# ELEKTRA-BENCH_v0_1-20240103.net
KiCad netlist of a schematic drawn in EAGLE
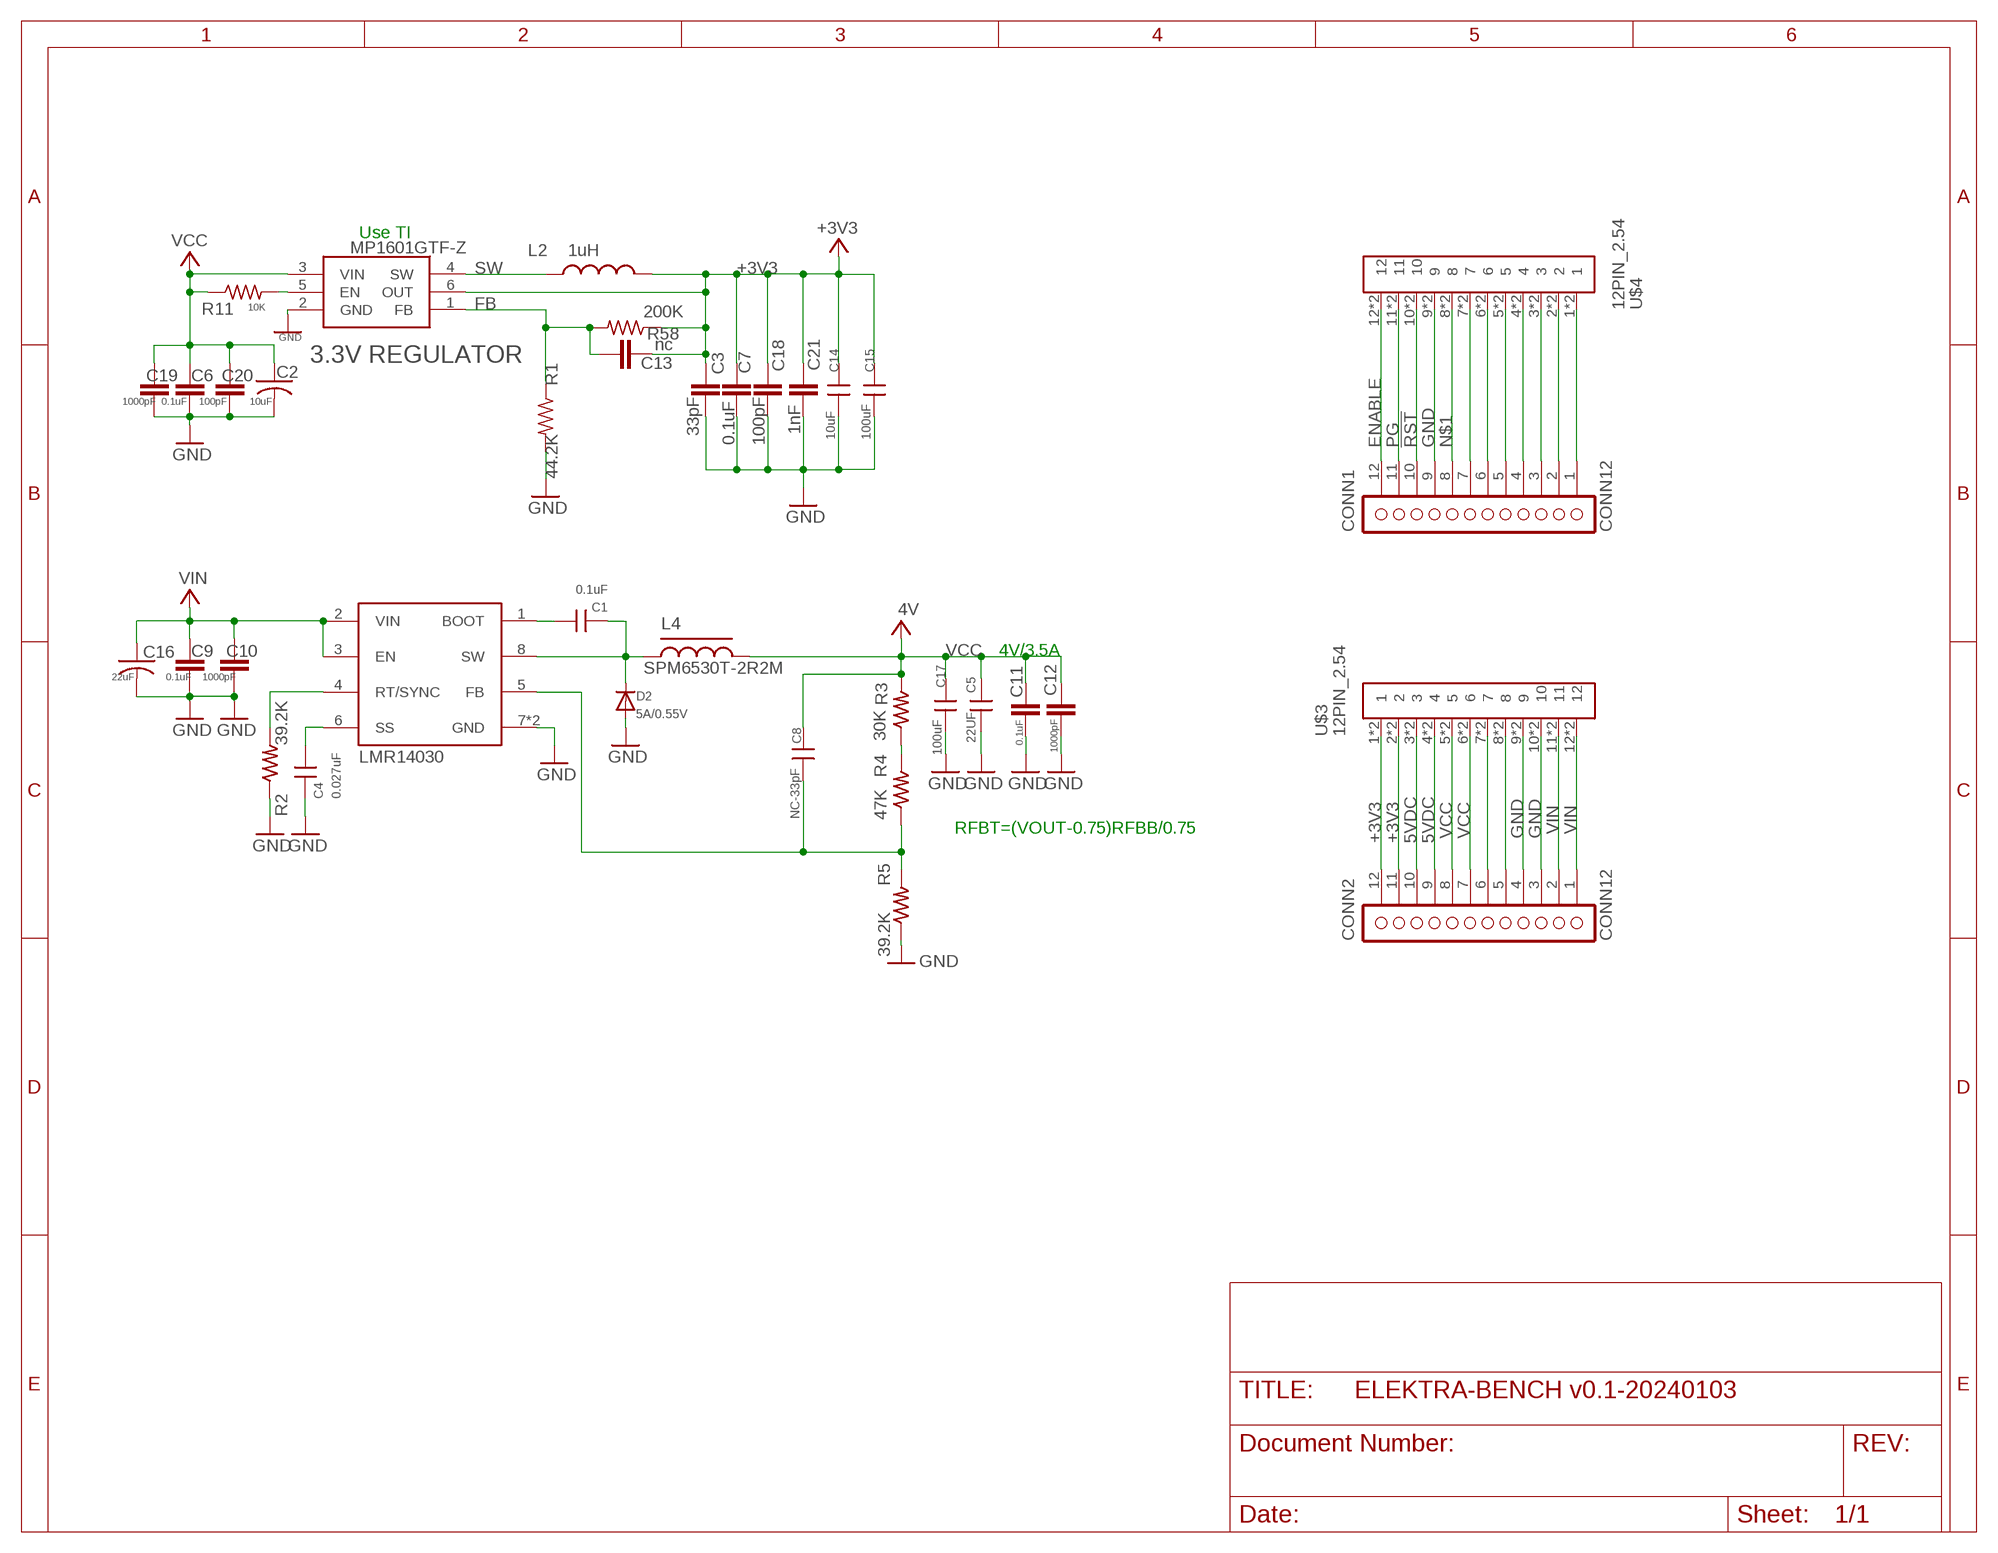
[diagram p0: schematic, sheet 1]

(export (version "E")
  (design (tool "Eeschema 10.0.6"))
  (components
    (comp (ref "C1")
      (value "0.1uF")
      (footprint "eagle-import:C0402")
      (libsource (lib "eagle-import") (part "particle SZ_21650216_CAP0402A"))
    )
    (comp (ref "C2")
      (value "10uF")
      (footprint "eagle-import:C0603_B")
      (libsource (lib "eagle-import") (part "C-US0603"))
    )
    (comp (ref "C3")
      (value "33pF")
      (footprint "eagle-import:C0402_B")
      (libsource (lib "eagle-import") (part "CAP_1"))
    )
    (comp (ref "C4")
      (value "0.027uF")
      (footprint "eagle-import:C0402")
      (libsource (lib "eagle-import") (part "particle SZ_21650216_CAP0402A"))
    )
    (comp (ref "C5")
      (value "22UF")
      (footprint "eagle-import:C0805")
      (libsource (lib "eagle-import") (part "CAPC0805"))
    )
    (comp (ref "C6")
      (value "0.1uF")
      (footprint "eagle-import:C0402_B")
      (libsource (lib "eagle-import") (part "CAP_1"))
    )
    (comp (ref "C7")
      (value "0.1uF")
      (footprint "eagle-import:C0402_B")
      (libsource (lib "eagle-import") (part "CAP_1"))
    )
    (comp (ref "C8")
      (value "NC-33pF")
      (footprint "eagle-import:C0402")
      (libsource (lib "eagle-import") (part "particle SZ_21650216_CAP0402A"))
    )
    (comp (ref "C9")
      (value "0.1uF")
      (footprint "eagle-import:C0402_B")
      (libsource (lib "eagle-import") (part "CAP_1"))
    )
    (comp (ref "C10")
      (value "1000pF")
      (footprint "eagle-import:C0402_B")
      (libsource (lib "eagle-import") (part "CAP_1"))
    )
    (comp (ref "C11")
      (value "0.1uF")
      (footprint "eagle-import:C0402_B")
      (libsource (lib "eagle-import") (part "CAP_1"))
    )
    (comp (ref "C12")
      (value "1000pF")
      (footprint "eagle-import:C0402_B")
      (libsource (lib "eagle-import") (part "CAP_1"))
    )
    (comp (ref "C13")
      (value "nc")
      (footprint "eagle-import:C0402_B")
      (libsource (lib "eagle-import") (part "CAP_1"))
    )
    (comp (ref "C14")
      (value "10uF")
      (footprint "eagle-import:C0805")
      (libsource (lib "eagle-import") (part "CAPC0805"))
    )
    (comp (ref "C15")
      (value "100uF")
      (footprint "eagle-import:C1206")
      (libsource (lib "eagle-import") (part "CAPC1206"))
    )
    (comp (ref "C16")
      (value "22uF")
      (footprint "eagle-import:C0603_B")
      (libsource (lib "eagle-import") (part "C-US0603"))
    )
    (comp (ref "C17")
      (value "100uF")
      (footprint "eagle-import:C1206")
      (libsource (lib "eagle-import") (part "CAPC1206"))
    )
    (comp (ref "C18")
      (value "100pF")
      (footprint "eagle-import:C0402_B")
      (libsource (lib "eagle-import") (part "CAP_1"))
    )
    (comp (ref "C19")
      (value "1000pF")
      (footprint "eagle-import:C0402_B")
      (libsource (lib "eagle-import") (part "CAP_1"))
    )
    (comp (ref "C20")
      (value "100pF")
      (footprint "eagle-import:C0402_B")
      (libsource (lib "eagle-import") (part "CAP_1"))
    )
    (comp (ref "C21")
      (value "1nF")
      (footprint "eagle-import:C0402_B")
      (libsource (lib "eagle-import") (part "CAP_1"))
    )
    (comp (ref "CONN1")
      (value "CONN12")
      (footprint "eagle-import:1X12_SMD_STRAIGHT")
      (libsource (lib "eagle-import") (part "CONN12"))
    )
    (comp (ref "CONN2")
      (value "CONN12")
      (footprint "eagle-import:1X12_SMD_STRAIGHT")
      (libsource (lib "eagle-import") (part "CONN12"))
    )
    (comp (ref "D2")
      (value "5A/0.55V")
      (footprint "eagle-import:SMADIODE")
      (libsource (lib "eagle-import") (part "DIODESMA"))
    )
    (comp (ref "L2")
      (value "1uH")
      (footprint "eagle-import:INDUCTOR-VLS-E")
      (libsource (lib "eagle-import") (part "INDUCTOR-SPARKFUNVLS3012ET-4R7M"))
    )
    (comp (ref "L4")
      (value "SPM6530T-2R2M")
      (footprint "eagle-import:INDCUTOR_SPM6530")
      (libsource (lib "eagle-import") (part "INDUCTOR"))
    )
    (comp (ref "R1")
      (value "44.2K")
      (footprint "eagle-import:R0402_B")
      (libsource (lib "eagle-import") (part "R-US_"))
    )
    (comp (ref "R2")
      (value "39.2K")
      (footprint "eagle-import:R-0402S")
      (libsource (lib "eagle-import") (part "RES0402S"))
    )
    (comp (ref "R3")
      (value "30K")
      (footprint "eagle-import:R-0402S")
      (libsource (lib "eagle-import") (part "RES0402S"))
    )
    (comp (ref "R4")
      (value "47K")
      (footprint "eagle-import:R-0402S")
      (libsource (lib "eagle-import") (part "RES0402S"))
    )
    (comp (ref "R5")
      (value "39.2K")
      (footprint "eagle-import:R-0402S")
      (libsource (lib "eagle-import") (part "RES0402S"))
    )
    (comp (ref "R11")
      (value "10K")
      (footprint "eagle-import:R0402_B")
      (libsource (lib "eagle-import") (part "Spark_R-US_"))
    )
    (comp (ref "R58")
      (value "200K")
      (footprint "eagle-import:R0402_B")
      (libsource (lib "eagle-import") (part "R-US_"))
    )
    (comp (ref "U$3")
      (value "12PIN_2.54")
      (footprint "eagle-import:12PIN_2.54")
      (libsource (lib "eagle-import") (part "12PIN_2.54"))
    )
    (comp (ref "U$4")
      (value "12PIN_2.54")
      (footprint "eagle-import:12PIN_2.54")
      (libsource (lib "eagle-import") (part "12PIN_2.54"))
    )
    (comp (ref "U2")
      (value "LMR14030")
      (footprint "eagle-import:SO_POWERPAD_8")
      (libsource (lib "eagle-import") (part "LMR14030"))
    )
    (comp (ref "U3")
      (value "MP1601GTF-Z")
      (footprint "eagle-import:SOTFL50P160X60-6N")
      (libsource (lib "eagle-import") (part "MP1601GTF-Z"))
    )
  )
  (nets
    (net (code "1") (name "+3V3") (class "Default")
      (node (ref "C13") (pin "1") (pinfunction "P$1_1") (pintype "passive"))
      (node (ref "C14") (pin "1") (pinfunction "1_1") (pintype "bidirectional"))
      (node (ref "C15") (pin "1") (pinfunction "1_1") (pintype "bidirectional"))
      (node (ref "C18") (pin "2") (pinfunction "P$2_2") (pintype "passive"))
      (node (ref "C21") (pin "2") (pinfunction "P$2_2") (pintype "passive"))
      (node (ref "C3") (pin "2") (pinfunction "P$2_2") (pintype "passive"))
      (node (ref "C7") (pin "2") (pinfunction "P$2_2") (pintype "passive"))
      (node (ref "CONN2") (pin "11") (pinfunction "11_11") (pintype "passive"))
      (node (ref "CONN2") (pin "12") (pinfunction "12_12") (pintype "passive"))
      (node (ref "L2") (pin "P$2") (pinfunction "2_P$2") (pintype "passive"))
      (node (ref "R58") (pin "1") (pinfunction "1_1") (pintype "passive"))
      (node (ref "U$3") (pin "1") (pinfunction "1_1") (pintype "bidirectional"))
      (node (ref "U$3") (pin "2") (pinfunction "2_2") (pintype "bidirectional"))
      (node (ref "U$3") (pin "P$1") (pinfunction "1_P$1") (pintype "bidirectional"))
      (node (ref "U$3") (pin "P$2") (pinfunction "2_P$2") (pintype "bidirectional"))
      (node (ref "U3") (pin "6") (pinfunction "OUT_6") (pintype "bidirectional"))
    )
    (net (code "2") (name "/5VDC") (class "Default")
      (node (ref "CONN2") (pin "10") (pinfunction "10_10") (pintype "passive"))
      (node (ref "CONN2") (pin "9") (pinfunction "9_9") (pintype "passive"))
      (node (ref "U$3") (pin "3") (pinfunction "3_3") (pintype "bidirectional"))
      (node (ref "U$3") (pin "4") (pinfunction "4_4") (pintype "bidirectional"))
      (node (ref "U$3") (pin "P$3") (pinfunction "3_P$3") (pintype "bidirectional"))
      (node (ref "U$3") (pin "P$4") (pinfunction "4_P$4") (pintype "bidirectional"))
    )
    (net (code "3") (name "/ENABLE") (class "Default")
      (node (ref "CONN1") (pin "12") (pinfunction "12_12") (pintype "passive"))
      (node (ref "U$4") (pin "12") (pinfunction "12_12") (pintype "bidirectional"))
      (node (ref "U$4") (pin "P$12") (pinfunction "12_P$12") (pintype "bidirectional"))
    )
    (net (code "4") (name "/FB") (class "Default")
      (node (ref "C13") (pin "2") (pinfunction "P$2_2") (pintype "passive"))
      (node (ref "R1") (pin "1") (pinfunction "1_1") (pintype "passive"))
      (node (ref "R58") (pin "2") (pinfunction "2_2") (pintype "passive"))
      (node (ref "U3") (pin "1") (pinfunction "FB_1") (pintype "bidirectional"))
    )
    (net (code "5") (name "/N$1") (class "Default")
      (node (ref "CONN1") (pin "8") (pinfunction "8_8") (pintype "passive"))
      (node (ref "U$4") (pin "8") (pinfunction "8_8") (pintype "bidirectional"))
      (node (ref "U$4") (pin "P$8") (pinfunction "8_P$8") (pintype "bidirectional"))
    )
    (net (code "6") (name "/PG") (class "Default")
      (node (ref "CONN1") (pin "11") (pinfunction "11_11") (pintype "passive"))
      (node (ref "U$4") (pin "11") (pinfunction "11_11") (pintype "bidirectional"))
      (node (ref "U$4") (pin "P$11") (pinfunction "11_P$11") (pintype "bidirectional"))
    )
    (net (code "7") (name "/SW") (class "Default")
      (node (ref "L2") (pin "P$1") (pinfunction "1_P$1") (pintype "passive"))
      (node (ref "U3") (pin "4") (pinfunction "SW_4") (pintype "bidirectional"))
    )
    (net (code "8") (name "/~{RST}") (class "Default")
      (node (ref "CONN1") (pin "10") (pinfunction "10_10") (pintype "passive"))
      (node (ref "U$4") (pin "10") (pinfunction "10_10") (pintype "bidirectional"))
      (node (ref "U$4") (pin "P$10") (pinfunction "10_P$10") (pintype "bidirectional"))
    )
    (net (code "9") (name "4V") (class "Default")
      (node (ref "C11") (pin "2") (pinfunction "P$2_2") (pintype "passive"))
      (node (ref "C12") (pin "2") (pinfunction "P$2_2") (pintype "passive"))
      (node (ref "C17") (pin "1") (pinfunction "1_1") (pintype "bidirectional"))
      (node (ref "C19") (pin "2") (pinfunction "P$2_2") (pintype "passive"))
      (node (ref "C2") (pin "1") (pinfunction "1_1") (pintype "passive"))
      (node (ref "C20") (pin "2") (pinfunction "P$2_2") (pintype "passive"))
      (node (ref "C5") (pin "1") (pinfunction "1_1") (pintype "bidirectional"))
      (node (ref "C6") (pin "2") (pinfunction "P$2_2") (pintype "passive"))
      (node (ref "C8") (pin "2") (pinfunction "2_2") (pintype "bidirectional"))
      (node (ref "CONN2") (pin "7") (pinfunction "7_7") (pintype "passive"))
      (node (ref "CONN2") (pin "8") (pinfunction "8_8") (pintype "passive"))
      (node (ref "L4") (pin "2") (pinfunction "2_2") (pintype "bidirectional"))
      (node (ref "R11") (pin "1") (pinfunction "1_1") (pintype "passive"))
      (node (ref "R3") (pin "2") (pinfunction "2_2") (pintype "bidirectional"))
      (node (ref "U$3") (pin "5") (pinfunction "5_5") (pintype "bidirectional"))
      (node (ref "U$3") (pin "6") (pinfunction "6_6") (pintype "bidirectional"))
      (node (ref "U$3") (pin "P$5") (pinfunction "5_P$5") (pintype "bidirectional"))
      (node (ref "U$3") (pin "P$6") (pinfunction "6_P$6") (pintype "bidirectional"))
      (node (ref "U3") (pin "3") (pinfunction "VIN_3") (pintype "bidirectional"))
    )
    (net (code "10") (name "GND") (class "Default")
      (node (ref "C10") (pin "1") (pinfunction "P$1_1") (pintype "passive"))
      (node (ref "C11") (pin "1") (pinfunction "P$1_1") (pintype "passive"))
      (node (ref "C12") (pin "1") (pinfunction "P$1_1") (pintype "passive"))
      (node (ref "C14") (pin "2") (pinfunction "2_2") (pintype "bidirectional"))
      (node (ref "C15") (pin "2") (pinfunction "2_2") (pintype "bidirectional"))
      (node (ref "C16") (pin "2") (pinfunction "2_2") (pintype "passive"))
      (node (ref "C17") (pin "2") (pinfunction "2_2") (pintype "bidirectional"))
      (node (ref "C18") (pin "1") (pinfunction "P$1_1") (pintype "passive"))
      (node (ref "C19") (pin "1") (pinfunction "P$1_1") (pintype "passive"))
      (node (ref "C2") (pin "2") (pinfunction "2_2") (pintype "passive"))
      (node (ref "C20") (pin "1") (pinfunction "P$1_1") (pintype "passive"))
      (node (ref "C21") (pin "1") (pinfunction "P$1_1") (pintype "passive"))
      (node (ref "C3") (pin "1") (pinfunction "P$1_1") (pintype "passive"))
      (node (ref "C4") (pin "2") (pinfunction "2_2") (pintype "bidirectional"))
      (node (ref "C5") (pin "2") (pinfunction "2_2") (pintype "bidirectional"))
      (node (ref "C6") (pin "1") (pinfunction "P$1_1") (pintype "passive"))
      (node (ref "C7") (pin "1") (pinfunction "P$1_1") (pintype "passive"))
      (node (ref "C9") (pin "1") (pinfunction "P$1_1") (pintype "passive"))
      (node (ref "CONN1") (pin "9") (pinfunction "9_9") (pintype "passive"))
      (node (ref "CONN2") (pin "3") (pinfunction "3_3") (pintype "passive"))
      (node (ref "CONN2") (pin "4") (pinfunction "4_4") (pintype "passive"))
      (node (ref "D2") (pin "A") (pinfunction "A_A") (pintype "passive"))
      (node (ref "R1") (pin "2") (pinfunction "2_2") (pintype "passive"))
      (node (ref "R2") (pin "1") (pinfunction "1_1") (pintype "bidirectional"))
      (node (ref "R5") (pin "1") (pinfunction "1_1") (pintype "bidirectional"))
      (node (ref "U$3") (pin "10") (pinfunction "10_10") (pintype "bidirectional"))
      (node (ref "U$3") (pin "9") (pinfunction "9_9") (pintype "bidirectional"))
      (node (ref "U$3") (pin "P$10") (pinfunction "10_P$10") (pintype "bidirectional"))
      (node (ref "U$3") (pin "P$9") (pinfunction "9_P$9") (pintype "bidirectional"))
      (node (ref "U$4") (pin "9") (pinfunction "9_9") (pintype "bidirectional"))
      (node (ref "U$4") (pin "P$9") (pinfunction "9_P$9") (pintype "bidirectional"))
      (node (ref "U2") (pin "7") (pinfunction "GND_7") (pintype "bidirectional"))
      (node (ref "U2") (pin "EP") (pinfunction "GND_EP") (pintype "bidirectional"))
      (node (ref "U3") (pin "2") (pinfunction "GND_2") (pintype "bidirectional"))
    )
    (net (code "11") (name "Net-(CONN1-Pad1)") (class "Default")
      (node (ref "CONN1") (pin "1") (pinfunction "1_1") (pintype "passive"))
      (node (ref "U$4") (pin "1") (pinfunction "1_1") (pintype "bidirectional"))
      (node (ref "U$4") (pin "P$1") (pinfunction "1_P$1") (pintype "bidirectional"))
    )
    (net (code "12") (name "Net-(CONN1-Pad2)") (class "Default")
      (node (ref "CONN1") (pin "2") (pinfunction "2_2") (pintype "passive"))
      (node (ref "U$4") (pin "2") (pinfunction "2_2") (pintype "bidirectional"))
      (node (ref "U$4") (pin "P$2") (pinfunction "2_P$2") (pintype "bidirectional"))
    )
    (net (code "13") (name "Net-(CONN1-Pad3)") (class "Default")
      (node (ref "CONN1") (pin "3") (pinfunction "3_3") (pintype "passive"))
      (node (ref "U$4") (pin "3") (pinfunction "3_3") (pintype "bidirectional"))
      (node (ref "U$4") (pin "P$3") (pinfunction "3_P$3") (pintype "bidirectional"))
    )
    (net (code "14") (name "Net-(CONN1-Pad4)") (class "Default")
      (node (ref "CONN1") (pin "4") (pinfunction "4_4") (pintype "passive"))
      (node (ref "U$4") (pin "4") (pinfunction "4_4") (pintype "bidirectional"))
      (node (ref "U$4") (pin "P$4") (pinfunction "4_P$4") (pintype "bidirectional"))
    )
    (net (code "15") (name "Net-(CONN1-Pad5)") (class "Default")
      (node (ref "CONN1") (pin "5") (pinfunction "5_5") (pintype "passive"))
      (node (ref "U$4") (pin "5") (pinfunction "5_5") (pintype "bidirectional"))
      (node (ref "U$4") (pin "P$5") (pinfunction "5_P$5") (pintype "bidirectional"))
    )
    (net (code "16") (name "Net-(CONN1-Pad6)") (class "Default")
      (node (ref "CONN1") (pin "6") (pinfunction "6_6") (pintype "passive"))
      (node (ref "U$4") (pin "6") (pinfunction "6_6") (pintype "bidirectional"))
      (node (ref "U$4") (pin "P$6") (pinfunction "6_P$6") (pintype "bidirectional"))
    )
    (net (code "17") (name "Net-(CONN1-Pad7)") (class "Default")
      (node (ref "CONN1") (pin "7") (pinfunction "7_7") (pintype "passive"))
      (node (ref "U$4") (pin "7") (pinfunction "7_7") (pintype "bidirectional"))
      (node (ref "U$4") (pin "P$7") (pinfunction "7_P$7") (pintype "bidirectional"))
    )
    (net (code "18") (name "Net-(CONN2-Pad5)") (class "Default")
      (node (ref "CONN2") (pin "5") (pinfunction "5_5") (pintype "passive"))
      (node (ref "U$3") (pin "8") (pinfunction "8_8") (pintype "bidirectional"))
      (node (ref "U$3") (pin "P$8") (pinfunction "8_P$8") (pintype "bidirectional"))
    )
    (net (code "19") (name "Net-(CONN2-Pad6)") (class "Default")
      (node (ref "CONN2") (pin "6") (pinfunction "6_6") (pintype "passive"))
      (node (ref "U$3") (pin "7") (pinfunction "7_7") (pintype "bidirectional"))
      (node (ref "U$3") (pin "P$7") (pinfunction "7_P$7") (pintype "bidirectional"))
    )
    (net (code "20") (name "Net-(R3-Pad1)") (class "Default")
      (node (ref "R3") (pin "1") (pinfunction "1_1") (pintype "bidirectional"))
      (node (ref "R4") (pin "2") (pinfunction "2_2") (pintype "bidirectional"))
    )
    (net (code "21") (name "Net-(U2-BOOT)") (class "Default")
      (node (ref "C1") (pin "1") (pinfunction "1_1") (pintype "bidirectional"))
      (node (ref "U2") (pin "1") (pinfunction "BOOT_1") (pintype "bidirectional"))
    )
    (net (code "22") (name "Net-(U2-FB)") (class "Default")
      (node (ref "C8") (pin "1") (pinfunction "1_1") (pintype "bidirectional"))
      (node (ref "R4") (pin "1") (pinfunction "1_1") (pintype "bidirectional"))
      (node (ref "R5") (pin "2") (pinfunction "2_2") (pintype "bidirectional"))
      (node (ref "U2") (pin "5") (pinfunction "FB_5") (pintype "bidirectional"))
    )
    (net (code "23") (name "Net-(U2-RT{slash}SYNC)") (class "Default")
      (node (ref "R2") (pin "2") (pinfunction "2_2") (pintype "bidirectional"))
      (node (ref "U2") (pin "4") (pinfunction "RT/SYNC_4") (pintype "bidirectional"))
    )
    (net (code "24") (name "Net-(U2-SS)") (class "Default")
      (node (ref "C4") (pin "1") (pinfunction "1_1") (pintype "bidirectional"))
      (node (ref "U2") (pin "6") (pinfunction "SS_6") (pintype "bidirectional"))
    )
    (net (code "25") (name "Net-(U2-SW)") (class "Default")
      (node (ref "C1") (pin "2") (pinfunction "2_2") (pintype "bidirectional"))
      (node (ref "D2") (pin "C") (pinfunction "C_C") (pintype "passive"))
      (node (ref "L4") (pin "1") (pinfunction "1_1") (pintype "bidirectional"))
      (node (ref "U2") (pin "8") (pinfunction "SW_8") (pintype "bidirectional"))
    )
    (net (code "26") (name "Net-(U3-EN)") (class "Default")
      (node (ref "R11") (pin "2") (pinfunction "2_2") (pintype "passive"))
      (node (ref "U3") (pin "5") (pinfunction "EN_5") (pintype "bidirectional"))
    )
    (net (code "27") (name "VIN") (class "Default")
      (node (ref "C10") (pin "2") (pinfunction "P$2_2") (pintype "passive"))
      (node (ref "C16") (pin "1") (pinfunction "1_1") (pintype "passive"))
      (node (ref "C9") (pin "2") (pinfunction "P$2_2") (pintype "passive"))
      (node (ref "CONN2") (pin "1") (pinfunction "1_1") (pintype "passive"))
      (node (ref "CONN2") (pin "2") (pinfunction "2_2") (pintype "passive"))
      (node (ref "U$3") (pin "11") (pinfunction "11_11") (pintype "bidirectional"))
      (node (ref "U$3") (pin "12") (pinfunction "12_12") (pintype "bidirectional"))
      (node (ref "U$3") (pin "P$11") (pinfunction "11_P$11") (pintype "bidirectional"))
      (node (ref "U$3") (pin "P$12") (pinfunction "12_P$12") (pintype "bidirectional"))
      (node (ref "U2") (pin "2") (pinfunction "VIN_2") (pintype "bidirectional"))
      (node (ref "U2") (pin "3") (pinfunction "EN_3") (pintype "bidirectional"))
    )
  )
)
